# TPS709XX_30V_to_1V8.net
KiCad netlist of a schematic drawn in EAGLE
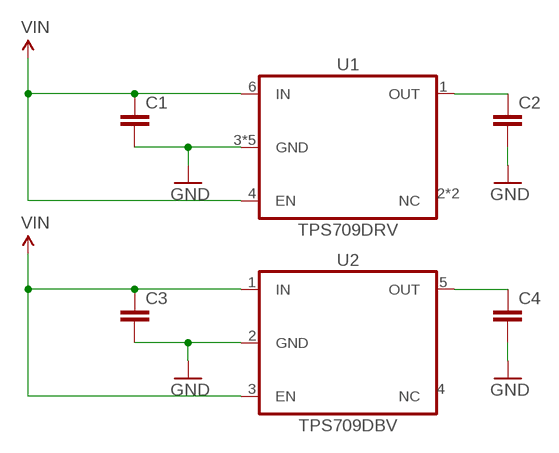
[diagram p0: schematic, sheet 1]

(export (version "E")
  (design (tool "Eeschema 10.0.6"))
  (components
    (comp (ref "C1")
      (value "C-EUC0402")
      (footprint "eagle-import:C0402")
      (libsource (lib "eagle-import") (part "C-EUC0402"))
    )
    (comp (ref "C2")
      (value "C-EUC0402")
      (footprint "eagle-import:C0402")
      (libsource (lib "eagle-import") (part "C-EUC0402"))
    )
    (comp (ref "C3")
      (value "C-EUC0603")
      (footprint "eagle-import:C0603")
      (libsource (lib "eagle-import") (part "C-EUC0603"))
    )
    (comp (ref "C4")
      (value "C-EUC0603")
      (footprint "eagle-import:C0603")
      (libsource (lib "eagle-import") (part "C-EUC0603"))
    )
    (comp (ref "U1")
      (value "TPS709DRV")
      (footprint "eagle-import:DRV")
      (libsource (lib "eagle-import") (part "TPS709DRV"))
    )
    (comp (ref "U2")
      (value "TPS709DBV")
      (footprint "eagle-import:DBV")
      (libsource (lib "eagle-import") (part "TPS709DBV"))
    )
  )
  (nets
    (net (code "1") (name "GND") (class "Default")
      (node (ref "C1") (pin "2") (pinfunction "2_2") (pintype "passive"))
      (node (ref "C2") (pin "2") (pinfunction "2_2") (pintype "passive"))
      (node (ref "C3") (pin "2") (pinfunction "2_2") (pintype "passive"))
      (node (ref "C4") (pin "2") (pinfunction "2_2") (pintype "passive"))
      (node (ref "U1") (pin "3") (pinfunction "GND_3") (pintype "passive"))
      (node (ref "U1") (pin "7") (pinfunction "GND_7") (pintype "passive"))
      (node (ref "U1") (pin "8") (pinfunction "GND_8") (pintype "passive"))
      (node (ref "U1") (pin "V1") (pinfunction "GND_V1") (pintype "passive"))
      (node (ref "U1") (pin "V2") (pinfunction "GND_V2") (pintype "passive"))
      (node (ref "U2") (pin "2") (pinfunction "GND_2") (pintype "passive"))
    )
    (net (code "2") (name "Net-(U1-OUT)") (class "Default")
      (node (ref "C2") (pin "1") (pinfunction "1_1") (pintype "passive"))
      (node (ref "U1") (pin "1") (pinfunction "OUT_1") (pintype "output"))
    )
    (net (code "3") (name "Net-(U2-OUT)") (class "Default")
      (node (ref "C4") (pin "1") (pinfunction "1_1") (pintype "passive"))
      (node (ref "U2") (pin "5") (pinfunction "OUT_5") (pintype "output"))
    )
    (net (code "4") (name "VIN") (class "Default")
      (node (ref "C1") (pin "1") (pinfunction "1_1") (pintype "passive"))
      (node (ref "C3") (pin "1") (pinfunction "1_1") (pintype "passive"))
      (node (ref "U1") (pin "4") (pinfunction "EN_4") (pintype "input"))
      (node (ref "U1") (pin "6") (pinfunction "IN_6") (pintype "input"))
      (node (ref "U2") (pin "1") (pinfunction "IN_1") (pintype "input"))
      (node (ref "U2") (pin "3") (pinfunction "EN_3") (pintype "input"))
    )
    (net (code "5") (name "unconnected-(U1-NC-Pad2)") (class "Default")
      (node (ref "U1") (pin "2") (pinfunction "NC_2") (pintype "no_connect"))
    )
    (net (code "6") (name "unconnected-(U1-NC-Pad5)") (class "Default")
      (node (ref "U1") (pin "5") (pinfunction "NC_5") (pintype "no_connect"))
    )
    (net (code "7") (name "unconnected-(U2-NC-Pad4)") (class "Default")
      (node (ref "U2") (pin "4") (pinfunction "NC_4") (pintype "no_connect"))
    )
  )
)
